# laser-tag.net
KiCad netlist of a schematic drawn in EAGLE
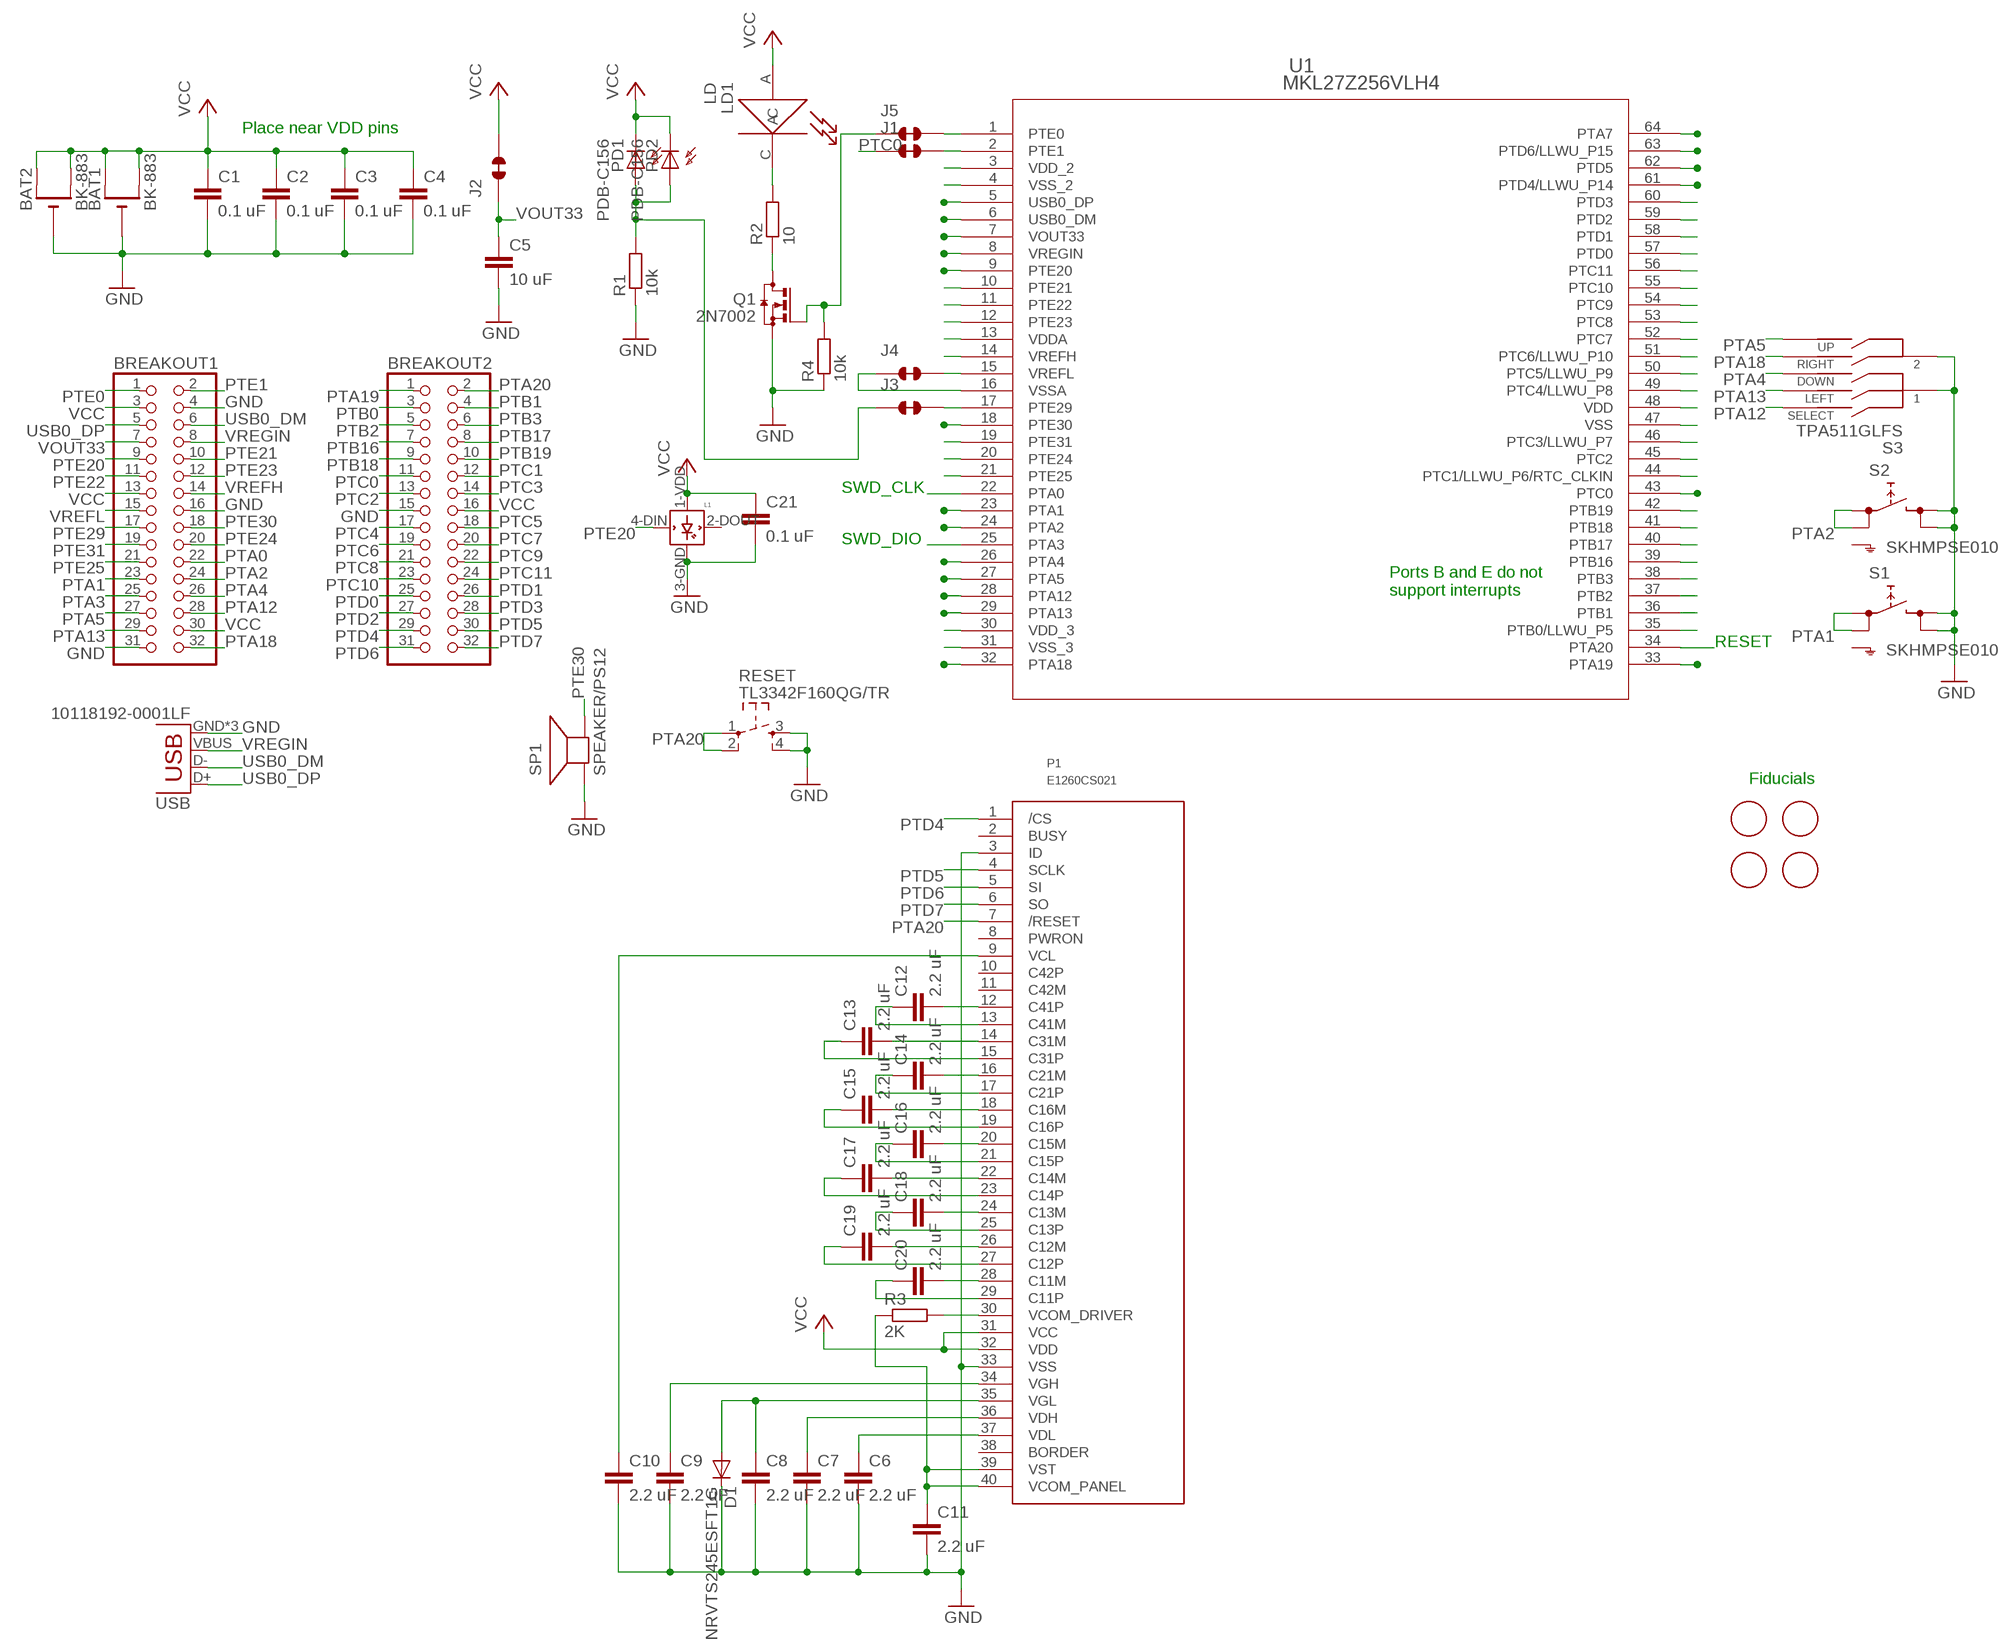
[diagram p0: schematic, sheet 1]

(export (version "E")
  (design (tool "Eeschema 10.0.6"))
  (components
    (comp (ref "BAT1")
      (value "BK-883")
      (footprint "eagle-import:CR2032-SMD")
      (libsource (lib "eagle-import") (part "CR2032SMT"))
    )
    (comp (ref "BAT2")
      (value "BK-883")
      (footprint "eagle-import:CR2032-SMD")
      (libsource (lib "eagle-import") (part "CR2032SMT"))
    )
    (comp (ref "BREAKOUT1")
      (value "PINHD-2X16")
      (footprint "eagle-import:2X16")
      (libsource (lib "eagle-import") (part "PINHD-2X16"))
    )
    (comp (ref "BREAKOUT2")
      (value "PINHD-2X16")
      (footprint "eagle-import:2X16")
      (libsource (lib "eagle-import") (part "PINHD-2X16"))
    )
    (comp (ref "C1")
      (value "0.1 uF")
      (footprint "eagle-import:C0603K")
      (libsource (lib "eagle-import") (part "C-EUC0603K"))
    )
    (comp (ref "C2")
      (value "0.1 uF")
      (footprint "eagle-import:C0603K")
      (libsource (lib "eagle-import") (part "C-EUC0603K"))
    )
    (comp (ref "C3")
      (value "0.1 uF")
      (footprint "eagle-import:C0603K")
      (libsource (lib "eagle-import") (part "C-EUC0603K"))
    )
    (comp (ref "C4")
      (value "0.1 uF")
      (footprint "eagle-import:C0603K")
      (libsource (lib "eagle-import") (part "C-EUC0603K"))
    )
    (comp (ref "C5")
      (value "10 uF")
      (footprint "eagle-import:C0603K")
      (libsource (lib "eagle-import") (part "C-EUC0603K"))
    )
    (comp (ref "C6")
      (value "2.2 uF")
      (footprint "eagle-import:C0603K")
      (libsource (lib "eagle-import") (part "C-EUC0603K"))
    )
    (comp (ref "C7")
      (value "2.2 uF")
      (footprint "eagle-import:C0603K")
      (libsource (lib "eagle-import") (part "C-EUC0603K"))
    )
    (comp (ref "C8")
      (value "2.2 uF")
      (footprint "eagle-import:C0603K")
      (libsource (lib "eagle-import") (part "C-EUC0603K"))
    )
    (comp (ref "C9")
      (value "2.2 uF")
      (footprint "eagle-import:C0603K")
      (libsource (lib "eagle-import") (part "C-EUC0603K"))
    )
    (comp (ref "C10")
      (value "2.2 uF")
      (footprint "eagle-import:C0603K")
      (libsource (lib "eagle-import") (part "C-EUC0603K"))
    )
    (comp (ref "C11")
      (value "2.2 uF")
      (footprint "eagle-import:C0603K")
      (libsource (lib "eagle-import") (part "C-EUC0603K"))
    )
    (comp (ref "C12")
      (value "2.2 uF")
      (footprint "eagle-import:C0603K")
      (libsource (lib "eagle-import") (part "C-EUC0603K"))
    )
    (comp (ref "C13")
      (value "2.2 uF")
      (footprint "eagle-import:C0603K")
      (libsource (lib "eagle-import") (part "C-EUC0603K"))
    )
    (comp (ref "C14")
      (value "2.2 uF")
      (footprint "eagle-import:C0603K")
      (libsource (lib "eagle-import") (part "C-EUC0603K"))
    )
    (comp (ref "C15")
      (value "2.2 uF")
      (footprint "eagle-import:C0603K")
      (libsource (lib "eagle-import") (part "C-EUC0603K"))
    )
    (comp (ref "C16")
      (value "2.2 uF")
      (footprint "eagle-import:C0603K")
      (libsource (lib "eagle-import") (part "C-EUC0603K"))
    )
    (comp (ref "C17")
      (value "2.2 uF")
      (footprint "eagle-import:C0603K")
      (libsource (lib "eagle-import") (part "C-EUC0603K"))
    )
    (comp (ref "C18")
      (value "2.2 uF")
      (footprint "eagle-import:C0603K")
      (libsource (lib "eagle-import") (part "C-EUC0603K"))
    )
    (comp (ref "C19")
      (value "2.2 uF")
      (footprint "eagle-import:C0603K")
      (libsource (lib "eagle-import") (part "C-EUC0603K"))
    )
    (comp (ref "C20")
      (value "2.2 uF")
      (footprint "eagle-import:C0603K")
      (libsource (lib "eagle-import") (part "C-EUC0603K"))
    )
    (comp (ref "C21")
      (value "0.1 uF")
      (footprint "eagle-import:C0603K")
      (libsource (lib "eagle-import") (part "C-EUC0603K"))
    )
    (comp (ref "D1")
      (value "NRVTS245ESFT1G")
      (footprint "eagle-import:SOD-123_MINI-SMA")
      (libsource (lib "eagle-import") (part "CGRM400-G1"))
    )
    (comp (ref "J1")
      (value "JUMPER_SOLDER_1X2_CLOSED")
      (footprint "eagle-import:JUMPER_SOLDER_1X2_CLOSED")
      (libsource (lib "eagle-import") (part "JUMPER_SOLDER_1X2_CLOSED"))
    )
    (comp (ref "J2")
      (value "JUMPER_SOLDER_1X2_CLOSED")
      (footprint "eagle-import:JUMPER_SOLDER_1X2_CLOSED")
      (libsource (lib "eagle-import") (part "JUMPER_SOLDER_1X2_CLOSED"))
    )
    (comp (ref "J3")
      (value "JUMPER_SOLDER_1X2_CLOSED")
      (footprint "eagle-import:JUMPER_SOLDER_1X2_CLOSED")
      (libsource (lib "eagle-import") (part "JUMPER_SOLDER_1X2_CLOSED"))
    )
    (comp (ref "J4")
      (value "JUMPER_SOLDER_1X2_CLOSED")
      (footprint "eagle-import:JUMPER_SOLDER_1X2_CLOSED")
      (libsource (lib "eagle-import") (part "JUMPER_SOLDER_1X2_CLOSED"))
    )
    (comp (ref "J5")
      (value "JUMPER_SOLDER_1X2_CLOSED")
      (footprint "eagle-import:JUMPER_SOLDER_1X2_CLOSED")
      (libsource (lib "eagle-import") (part "JUMPER_SOLDER_1X2_CLOSED"))
    )
    (comp (ref "L1")
      (value "WS2812B")
      (footprint "eagle-import:WS2812B")
      (libsource (lib "eagle-import") (part "WS2812B"))
    )
    (comp (ref "LD1")
      (value "LD")
      (footprint "eagle-import:LD-FLUSH-WITH-JUMPER")
      (libsource (lib "eagle-import") (part "LD"))
    )
    (comp (ref "P1")
      (value "E1260CS021")
      (footprint "eagle-import:E1260CS021_SLOT")
      (libsource (lib "eagle-import") (part "E1260CS021"))
    )
    (comp (ref "PD1")
      (value "PDB-C156")
      (footprint "eagle-import:PDB-C156-FLUSH")
      (libsource (lib "eagle-import") (part "PDB-C156"))
    )
    (comp (ref "PD2")
      (value "PDB-C156")
      (footprint "eagle-import:PDB-C156-FLUSH")
      (libsource (lib "eagle-import") (part "PDB-C156"))
    )
    (comp (ref "Q1")
      (value "2N7002")
      (footprint "eagle-import:SOT23")
      (libsource (lib "eagle-import") (part "BSS123"))
    )
    (comp (ref "R1")
      (value "10k")
      (footprint "eagle-import:R0603")
      (libsource (lib "eagle-import") (part "R-EU_R0603"))
    )
    (comp (ref "R2")
      (value "10")
      (footprint "eagle-import:R0603")
      (libsource (lib "eagle-import") (part "R-EU_R0603"))
    )
    (comp (ref "R3")
      (value "2K")
      (footprint "eagle-import:R0603")
      (libsource (lib "eagle-import") (part "R-EU_R0603"))
    )
    (comp (ref "R4")
      (value "10k")
      (footprint "eagle-import:R0603")
      (libsource (lib "eagle-import") (part "R-EU_R0603"))
    )
    (comp (ref "RESET")
      (value "TL3342F160QG/TR")
      (footprint "eagle-import:SW_TACT_SMALL")
      (libsource (lib "eagle-import") (part "SW_TACT_4P"))
    )
    (comp (ref "S1")
      (value "SKHMPSE010")
      (footprint "eagle-import:SKHMPXE010")
      (libsource (lib "eagle-import") (part "SKHMPE010S"))
    )
    (comp (ref "S2")
      (value "SKHMPSE010")
      (footprint "eagle-import:SKHMPXE010")
      (libsource (lib "eagle-import") (part "SKHMPE010S"))
    )
    (comp (ref "S3")
      (value "TPA511GLFS")
      (footprint "eagle-import:TPA511GLFS")
      (libsource (lib "eagle-import") (part "TPA511GLFS"))
    )
    (comp (ref "SP1")
      (value "SPEAKER/PS12")
      (footprint "eagle-import:PS12")
      (libsource (lib "eagle-import") (part "SPEAKER/PS12"))
    )
    (comp (ref "U$1")
      (value "FIDUCIAL")
      (footprint "eagle-import:FIDUCIAL_1MM")
      (libsource (lib "eagle-import") (part "FIDUCIAL"))
    )
    (comp (ref "U$2")
      (value "FIDUCIAL")
      (footprint "eagle-import:FIDUCIAL_1MM")
      (libsource (lib "eagle-import") (part "FIDUCIAL"))
    )
    (comp (ref "U$3")
      (value "FIDUCIAL")
      (footprint "eagle-import:FIDUCIAL_1MM")
      (libsource (lib "eagle-import") (part "FIDUCIAL"))
    )
    (comp (ref "U$4")
      (value "FIDUCIAL")
      (footprint "eagle-import:FIDUCIAL_1MM")
      (libsource (lib "eagle-import") (part "FIDUCIAL"))
    )
    (comp (ref "U1")
      (value "MKL27Z256VLH4")
      (footprint "eagle-import:LQFP-64_10X10X1.6")
      (fields (field (name "MANUFACTURER_PART_NUMBER") "mkl27z256vlh4"))
      (libsource (lib "eagle-import") (part "MKL27Z256VLH4"))
    )
    (comp (ref "USB")
      (value "10118192-0001LF")
      (footprint "eagle-import:USB-MICROB")
      (libsource (lib "eagle-import") (part "USB-MICROB"))
    )
  )
  (nets
    (net (code "1") (name "/PTA0") (class "Default")
      (node (ref "BREAKOUT1") (pin "22") (pinfunction "22_22") (pintype "passive"))
      (node (ref "U1") (pin "22") (pinfunction "PTA0_22") (pintype "bidirectional"))
    )
    (net (code "2") (name "/PTA1") (class "Default")
      (node (ref "BREAKOUT1") (pin "23") (pinfunction "23_23") (pintype "passive"))
      (node (ref "S1") (pin "1") (pinfunction "1.1_1") (pintype "passive"))
      (node (ref "S1") (pin "2") (pinfunction "1.2_2") (pintype "passive"))
      (node (ref "U1") (pin "23") (pinfunction "PTA1_23") (pintype "bidirectional"))
    )
    (net (code "3") (name "/PTA2") (class "Default")
      (node (ref "BREAKOUT1") (pin "24") (pinfunction "24_24") (pintype "passive"))
      (node (ref "S2") (pin "1") (pinfunction "1.1_1") (pintype "passive"))
      (node (ref "S2") (pin "2") (pinfunction "1.2_2") (pintype "passive"))
      (node (ref "U1") (pin "24") (pinfunction "PTA2_24") (pintype "bidirectional"))
    )
    (net (code "4") (name "/PTA3") (class "Default")
      (node (ref "BREAKOUT1") (pin "25") (pinfunction "25_25") (pintype "passive"))
      (node (ref "U1") (pin "25") (pinfunction "PTA3_25") (pintype "bidirectional"))
    )
    (net (code "5") (name "/PTA4") (class "Default")
      (node (ref "BREAKOUT1") (pin "26") (pinfunction "26_26") (pintype "passive"))
      (node (ref "S3") (pin "4") (pinfunction "DOWN_4") (pintype "bidirectional"))
      (node (ref "U1") (pin "26") (pinfunction "PTA4_26") (pintype "bidirectional"))
    )
    (net (code "6") (name "/PTA5") (class "Default")
      (node (ref "BREAKOUT1") (pin "27") (pinfunction "27_27") (pintype "passive"))
      (node (ref "S3") (pin "3") (pinfunction "UP_3") (pintype "bidirectional"))
      (node (ref "U1") (pin "27") (pinfunction "PTA5_27") (pintype "bidirectional"))
    )
    (net (code "7") (name "/PTA12") (class "Default")
      (node (ref "BREAKOUT1") (pin "28") (pinfunction "28_28") (pintype "passive"))
      (node (ref "S3") (pin "5") (pinfunction "SELECT_5") (pintype "bidirectional"))
      (node (ref "U1") (pin "28") (pinfunction "PTA12_28") (pintype "bidirectional"))
    )
    (net (code "8") (name "/PTA13") (class "Default")
      (node (ref "BREAKOUT1") (pin "29") (pinfunction "29_29") (pintype "passive"))
      (node (ref "S3") (pin "7") (pinfunction "LEFT_7") (pintype "bidirectional"))
      (node (ref "U1") (pin "29") (pinfunction "PTA13_29") (pintype "bidirectional"))
    )
    (net (code "9") (name "/PTA18") (class "Default")
      (node (ref "BREAKOUT1") (pin "32") (pinfunction "32_32") (pintype "passive"))
      (node (ref "S3") (pin "6") (pinfunction "RIGHT_6") (pintype "bidirectional"))
      (node (ref "U1") (pin "32") (pinfunction "PTA18_32") (pintype "bidirectional"))
    )
    (net (code "10") (name "/PTA19") (class "Default")
      (node (ref "BREAKOUT2") (pin "1") (pinfunction "1_1") (pintype "passive"))
      (node (ref "U1") (pin "33") (pinfunction "PTA19_33") (pintype "bidirectional"))
    )
    (net (code "11") (name "/PTA20") (class "Default")
      (node (ref "BREAKOUT2") (pin "2") (pinfunction "2_2") (pintype "passive"))
      (node (ref "P1") (pin "7") (pinfunction "/RESET_7") (pintype "input"))
      (node (ref "RESET") (pin "1") (pinfunction "1_1") (pintype "passive"))
      (node (ref "RESET") (pin "2") (pinfunction "2_2") (pintype "passive"))
      (node (ref "U1") (pin "34") (pinfunction "PTA20_34") (pintype "bidirectional"))
    )
    (net (code "12") (name "/PTB0") (class "Default")
      (node (ref "BREAKOUT2") (pin "3") (pinfunction "3_3") (pintype "passive"))
      (node (ref "U1") (pin "35") (pinfunction "PTB0/LLWU_P5_35") (pintype "bidirectional"))
    )
    (net (code "13") (name "/PTB1") (class "Default")
      (node (ref "BREAKOUT2") (pin "4") (pinfunction "4_4") (pintype "passive"))
      (node (ref "U1") (pin "36") (pinfunction "PTB1_36") (pintype "bidirectional"))
    )
    (net (code "14") (name "/PTB2") (class "Default")
      (node (ref "BREAKOUT2") (pin "5") (pinfunction "5_5") (pintype "passive"))
      (node (ref "U1") (pin "37") (pinfunction "PTB2_37") (pintype "bidirectional"))
    )
    (net (code "15") (name "/PTB3") (class "Default")
      (node (ref "BREAKOUT2") (pin "6") (pinfunction "6_6") (pintype "passive"))
      (node (ref "U1") (pin "38") (pinfunction "PTB3_38") (pintype "bidirectional"))
    )
    (net (code "16") (name "/PTB16") (class "Default")
      (node (ref "BREAKOUT2") (pin "7") (pinfunction "7_7") (pintype "passive"))
      (node (ref "U1") (pin "39") (pinfunction "PTB16_39") (pintype "bidirectional"))
    )
    (net (code "17") (name "/PTB17") (class "Default")
      (node (ref "BREAKOUT2") (pin "8") (pinfunction "8_8") (pintype "passive"))
      (node (ref "U1") (pin "40") (pinfunction "PTB17_40") (pintype "bidirectional"))
    )
    (net (code "18") (name "/PTB18") (class "Default")
      (node (ref "BREAKOUT2") (pin "9") (pinfunction "9_9") (pintype "passive"))
      (node (ref "U1") (pin "41") (pinfunction "PTB18_41") (pintype "bidirectional"))
    )
    (net (code "19") (name "/PTB19") (class "Default")
      (node (ref "BREAKOUT2") (pin "10") (pinfunction "10_10") (pintype "passive"))
      (node (ref "U1") (pin "42") (pinfunction "PTB19_42") (pintype "bidirectional"))
    )
    (net (code "20") (name "/PTC0") (class "Default")
      (node (ref "BREAKOUT2") (pin "11") (pinfunction "11_11") (pintype "passive"))
      (node (ref "J1") (pin "1") (pinfunction "1_1") (pintype "passive"))
      (node (ref "U1") (pin "43") (pinfunction "PTC0_43") (pintype "bidirectional"))
    )
    (net (code "21") (name "/PTC1") (class "Default")
      (node (ref "BREAKOUT2") (pin "12") (pinfunction "12_12") (pintype "passive"))
      (node (ref "U1") (pin "44") (pinfunction "PTC1/LLWU_P6/RTC_CLKIN_44") (pintype "bidirectional"))
    )
    (net (code "22") (name "/PTC2") (class "Default")
      (node (ref "BREAKOUT2") (pin "13") (pinfunction "13_13") (pintype "passive"))
      (node (ref "U1") (pin "45") (pinfunction "PTC2_45") (pintype "bidirectional"))
    )
    (net (code "23") (name "/PTC3") (class "Default")
      (node (ref "BREAKOUT2") (pin "14") (pinfunction "14_14") (pintype "passive"))
      (node (ref "U1") (pin "46") (pinfunction "PTC3/LLWU_P7_46") (pintype "bidirectional"))
    )
    (net (code "24") (name "/PTC4") (class "Default")
      (node (ref "BREAKOUT2") (pin "17") (pinfunction "17_17") (pintype "passive"))
      (node (ref "U1") (pin "49") (pinfunction "PTC4/LLWU_P8_49") (pintype "bidirectional"))
    )
    (net (code "25") (name "/PTC5") (class "Default")
      (node (ref "BREAKOUT2") (pin "18") (pinfunction "18_18") (pintype "passive"))
      (node (ref "U1") (pin "50") (pinfunction "PTC5/LLWU_P9_50") (pintype "bidirectional"))
    )
    (net (code "26") (name "/PTC6") (class "Default")
      (node (ref "BREAKOUT2") (pin "19") (pinfunction "19_19") (pintype "passive"))
      (node (ref "U1") (pin "51") (pinfunction "PTC6/LLWU_P10_51") (pintype "bidirectional"))
    )
    (net (code "27") (name "/PTC7") (class "Default")
      (node (ref "BREAKOUT2") (pin "20") (pinfunction "20_20") (pintype "passive"))
      (node (ref "U1") (pin "52") (pinfunction "PTC7_52") (pintype "bidirectional"))
    )
    (net (code "28") (name "/PTC8") (class "Default")
      (node (ref "BREAKOUT2") (pin "21") (pinfunction "21_21") (pintype "passive"))
      (node (ref "U1") (pin "53") (pinfunction "PTC8_53") (pintype "bidirectional"))
    )
    (net (code "29") (name "/PTC9") (class "Default")
      (node (ref "BREAKOUT2") (pin "22") (pinfunction "22_22") (pintype "passive"))
      (node (ref "U1") (pin "54") (pinfunction "PTC9_54") (pintype "bidirectional"))
    )
    (net (code "30") (name "/PTC10") (class "Default")
      (node (ref "BREAKOUT2") (pin "23") (pinfunction "23_23") (pintype "passive"))
      (node (ref "U1") (pin "55") (pinfunction "PTC10_55") (pintype "bidirectional"))
    )
    (net (code "31") (name "/PTC11") (class "Default")
      (node (ref "BREAKOUT2") (pin "24") (pinfunction "24_24") (pintype "passive"))
      (node (ref "U1") (pin "56") (pinfunction "PTC11_56") (pintype "bidirectional"))
    )
    (net (code "32") (name "/PTD0") (class "Default")
      (node (ref "BREAKOUT2") (pin "25") (pinfunction "25_25") (pintype "passive"))
      (node (ref "U1") (pin "57") (pinfunction "PTD0_57") (pintype "bidirectional"))
    )
    (net (code "33") (name "/PTD1") (class "Default")
      (node (ref "BREAKOUT2") (pin "26") (pinfunction "26_26") (pintype "passive"))
      (node (ref "U1") (pin "58") (pinfunction "PTD1_58") (pintype "bidirectional"))
    )
    (net (code "34") (name "/PTD2") (class "Default")
      (node (ref "BREAKOUT2") (pin "27") (pinfunction "27_27") (pintype "passive"))
      (node (ref "U1") (pin "59") (pinfunction "PTD2_59") (pintype "bidirectional"))
    )
    (net (code "35") (name "/PTD3") (class "Default")
      (node (ref "BREAKOUT2") (pin "28") (pinfunction "28_28") (pintype "passive"))
      (node (ref "U1") (pin "60") (pinfunction "PTD3_60") (pintype "bidirectional"))
    )
    (net (code "36") (name "/PTD4") (class "Default")
      (node (ref "BREAKOUT2") (pin "29") (pinfunction "29_29") (pintype "passive"))
      (node (ref "P1") (pin "1") (pinfunction "/CS_1") (pintype "input"))
      (node (ref "U1") (pin "61") (pinfunction "PTD4/LLWU_P14_61") (pintype "bidirectional"))
    )
    (net (code "37") (name "/PTD5") (class "Default")
      (node (ref "BREAKOUT2") (pin "30") (pinfunction "30_30") (pintype "passive"))
      (node (ref "P1") (pin "4") (pinfunction "SCLK_4") (pintype "input"))
      (node (ref "U1") (pin "62") (pinfunction "PTD5_62") (pintype "bidirectional"))
    )
    (net (code "38") (name "/PTD6") (class "Default")
      (node (ref "BREAKOUT2") (pin "31") (pinfunction "31_31") (pintype "passive"))
      (node (ref "P1") (pin "5") (pinfunction "SI_5") (pintype "input"))
      (node (ref "U1") (pin "63") (pinfunction "PTD6/LLWU_P15_63") (pintype "bidirectional"))
    )
    (net (code "39") (name "/PTD7") (class "Default")
      (node (ref "BREAKOUT2") (pin "32") (pinfunction "32_32") (pintype "passive"))
      (node (ref "P1") (pin "6") (pinfunction "SO_6") (pintype "output"))
      (node (ref "U1") (pin "64") (pinfunction "PTA7_64") (pintype "bidirectional"))
    )
    (net (code "40") (name "/PTE0") (class "Default")
      (node (ref "BREAKOUT1") (pin "1") (pinfunction "1_1") (pintype "passive"))
      (node (ref "J5") (pin "2") (pinfunction "2_2") (pintype "passive"))
      (node (ref "U1") (pin "1") (pinfunction "PTE0_1") (pintype "bidirectional"))
    )
    (net (code "41") (name "/PTE1") (class "Default")
      (node (ref "BREAKOUT1") (pin "2") (pinfunction "2_2") (pintype "passive"))
      (node (ref "J1") (pin "2") (pinfunction "2_2") (pintype "passive"))
      (node (ref "U1") (pin "2") (pinfunction "PTE1_2") (pintype "bidirectional"))
    )
    (net (code "42") (name "/PTE20") (class "Default")
      (node (ref "BREAKOUT1") (pin "9") (pinfunction "9_9") (pintype "passive"))
      (node (ref "L1") (pin "4-DIN") (pinfunction "DIN_4-DIN") (pintype "input"))
      (node (ref "U1") (pin "9") (pinfunction "PTE20_9") (pintype "bidirectional"))
    )
    (net (code "43") (name "/PTE21") (class "Default")
      (node (ref "BREAKOUT1") (pin "10") (pinfunction "10_10") (pintype "passive"))
      (node (ref "U1") (pin "10") (pinfunction "PTE21_10") (pintype "bidirectional"))
    )
    (net (code "44") (name "/PTE22") (class "Default")
      (node (ref "BREAKOUT1") (pin "11") (pinfunction "11_11") (pintype "passive"))
      (node (ref "U1") (pin "11") (pinfunction "PTE22_11") (pintype "bidirectional"))
    )
    (net (code "45") (name "/PTE23") (class "Default")
      (node (ref "BREAKOUT1") (pin "12") (pinfunction "12_12") (pintype "passive"))
      (node (ref "U1") (pin "12") (pinfunction "PTE23_12") (pintype "bidirectional"))
    )
    (net (code "46") (name "/PTE24") (class "Default")
      (node (ref "BREAKOUT1") (pin "20") (pinfunction "20_20") (pintype "passive"))
      (node (ref "U1") (pin "20") (pinfunction "PTE24_20") (pintype "bidirectional"))
    )
    (net (code "47") (name "/PTE25") (class "Default")
      (node (ref "BREAKOUT1") (pin "21") (pinfunction "21_21") (pintype "passive"))
      (node (ref "U1") (pin "21") (pinfunction "PTE25_21") (pintype "bidirectional"))
    )
    (net (code "48") (name "/PTE29") (class "Default")
      (node (ref "BREAKOUT1") (pin "17") (pinfunction "17_17") (pintype "passive"))
      (node (ref "J3") (pin "2") (pinfunction "2_2") (pintype "passive"))
      (node (ref "U1") (pin "17") (pinfunction "PTE29_17") (pintype "bidirectional"))
    )
    (net (code "49") (name "/PTE30") (class "Default")
      (node (ref "BREAKOUT1") (pin "18") (pinfunction "18_18") (pintype "passive"))
      (node (ref "SP1") (pin "P$2") (pinfunction "-_P$2") (pintype "passive"))
      (node (ref "U1") (pin "18") (pinfunction "PTE30_18") (pintype "bidirectional"))
    )
    (net (code "50") (name "/PTE31") (class "Default")
      (node (ref "BREAKOUT1") (pin "19") (pinfunction "19_19") (pintype "passive"))
      (node (ref "U1") (pin "19") (pinfunction "PTE31_19") (pintype "bidirectional"))
    )
    (net (code "51") (name "/USB0_DM") (class "Default")
      (node (ref "BREAKOUT1") (pin "6") (pinfunction "6_6") (pintype "passive"))
      (node (ref "U1") (pin "6") (pinfunction "USB0_DM_6") (pintype "passive"))
      (node (ref "USB") (pin "D-") (pinfunction "D-_D-") (pintype "bidirectional"))
    )
    (net (code "52") (name "/USB0_DP") (class "Default")
      (node (ref "BREAKOUT1") (pin "5") (pinfunction "5_5") (pintype "passive"))
      (node (ref "U1") (pin "5") (pinfunction "USB0_DP_5") (pintype "passive"))
      (node (ref "USB") (pin "D+") (pinfunction "D+_D+") (pintype "bidirectional"))
    )
    (net (code "53") (name "/VOUT33") (class "Default")
      (node (ref "BREAKOUT1") (pin "7") (pinfunction "7_7") (pintype "passive"))
      (node (ref "C5") (pin "1") (pinfunction "1_1") (pintype "passive"))
      (node (ref "J2") (pin "1") (pinfunction "1_1") (pintype "passive"))
      (node (ref "U1") (pin "7") (pinfunction "VOUT33_7") (pintype "output"))
    )
    (net (code "54") (name "/VREFH") (class "Default")
      (node (ref "BREAKOUT1") (pin "14") (pinfunction "14_14") (pintype "passive"))
      (node (ref "U1") (pin "14") (pinfunction "VREFH_14") (pintype "power_in"))
    )
    (net (code "55") (name "/VREFL") (class "Default")
      (node (ref "BREAKOUT1") (pin "15") (pinfunction "15_15") (pintype "passive"))
      (node (ref "J4") (pin "2") (pinfunction "2_2") (pintype "passive"))
      (node (ref "U1") (pin "15") (pinfunction "VREFL_15") (pintype "power_in"))
    )
    (net (code "56") (name "/VREGIN") (class "Default")
      (node (ref "BREAKOUT1") (pin "8") (pinfunction "8_8") (pintype "passive"))
      (node (ref "U1") (pin "8") (pinfunction "VREGIN_8") (pintype "input"))
      (node (ref "USB") (pin "VBUS") (pinfunction "VBUS_VBUS") (pintype "bidirectional"))
    )
    (net (code "57") (name "GND") (class "Default")
      (node (ref "BAT1") (pin "-") (pinfunction "-_-") (pintype "passive"))
      (node (ref "BAT2") (pin "-") (pinfunction "-_-") (pintype "passive"))
      (node (ref "BREAKOUT1") (pin "16") (pinfunction "16_16") (pintype "passive"))
      (node (ref "BREAKOUT1") (pin "31") (pinfunction "31_31") (pintype "passive"))
      (node (ref "BREAKOUT1") (pin "4") (pinfunction "4_4") (pintype "passive"))
      (node (ref "BREAKOUT2") (pin "15") (pinfunction "15_15") (pintype "passive"))
      (node (ref "C1") (pin "2") (pinfunction "2_2") (pintype "passive"))
      (node (ref "C10") (pin "2") (pinfunction "2_2") (pintype "passive"))
      (node (ref "C11") (pin "2") (pinfunction "2_2") (pintype "passive"))
      (node (ref "C2") (pin "2") (pinfunction "2_2") (pintype "passive"))
      (node (ref "C21") (pin "2") (pinfunction "2_2") (pintype "passive"))
      (node (ref "C3") (pin "2") (pinfunction "2_2") (pintype "passive"))
      (node (ref "C4") (pin "2") (pinfunction "2_2") (pintype "passive"))
      (node (ref "C5") (pin "2") (pinfunction "2_2") (pintype "passive"))
      (node (ref "C6") (pin "2") (pinfunction "2_2") (pintype "passive"))
      (node (ref "C7") (pin "2") (pinfunction "2_2") (pintype "passive"))
      (node (ref "C8") (pin "2") (pinfunction "2_2") (pintype "passive"))
      (node (ref "C9") (pin "2") (pinfunction "2_2") (pintype "passive"))
      (node (ref "D1") (pin "C") (pinfunction "C_C") (pintype "passive"))
      (node (ref "J4") (pin "1") (pinfunction "1_1") (pintype "passive"))
      (node (ref "L1") (pin "3-GND") (pinfunction "GND_3-GND") (pintype "bidirectional"))
      (node (ref "P1") (pin "3") (pinfunction "ID_3") (pintype "input"))
      (node (ref "P1") (pin "33") (pinfunction "VSS_33") (pintype "power_in"))
      (node (ref "Q1") (pin "2") (pinfunction "S_2") (pintype "passive"))
      (node (ref "R1") (pin "1") (pinfunction "1_1") (pintype "passive"))
      (node (ref "R4") (pin "1") (pinfunction "1_1") (pintype "passive"))
      (node (ref "RESET") (pin "3") (pinfunction "3_3") (pintype "passive"))
      (node (ref "RESET") (pin "4") (pinfunction "4_4") (pintype "passive"))
      (node (ref "S1") (pin "3") (pinfunction "2.1_3") (pintype "passive"))
      (node (ref "S1") (pin "4") (pinfunction "2.2_4") (pintype "passive"))
      (node (ref "S2") (pin "3") (pinfunction "2.1_3") (pintype "passive"))
      (node (ref "S2") (pin "4") (pinfunction "2.2_4") (pintype "passive"))
      (node (ref "S3") (pin "1") (pinfunction "1_1") (pintype "bidirectional"))
      (node (ref "S3") (pin "2") (pinfunction "2_2") (pintype "bidirectional"))
      (node (ref "SP1") (pin "P$1") (pinfunction "+_P$1") (pintype "passive"))
      (node (ref "U1") (pin "16") (pinfunction "VSSA_16") (pintype "power_in"))
      (node (ref "U1") (pin "31") (pinfunction "VSS_3_31") (pintype "power_in"))
      (node (ref "U1") (pin "4") (pinfunction "VSS_2_4") (pintype "power_in"))
      (node (ref "U1") (pin "47") (pinfunction "VSS_47") (pintype "power_in"))
      (node (ref "USB") (pin "GND") (pinfunction "GND_GND") (pintype "bidirectional"))
      (node (ref "USB") (pin "MT1") (pinfunction "GND_MT1") (pintype "bidirectional"))
      (node (ref "USB") (pin "MT2") (pinfunction "GND_MT2") (pintype "bidirectional"))
    )
    (net (code "58") (name "Net-(J3-Pad1)") (class "Default")
      (node (ref "J3") (pin "1") (pinfunction "1_1") (pintype "passive"))
      (node (ref "PD1") (pin "A") (pinfunction "A_A") (pintype "passive"))
      (node (ref "PD2") (pin "A") (pinfunction "A_A") (pintype "passive"))
      (node (ref "R1") (pin "2") (pinfunction "2_2") (pintype "passive"))
    )
    (net (code "59") (name "Net-(LD1-PadC)") (class "Default")
      (node (ref "LD1") (pin "C") (pinfunction "C_C") (pintype "passive"))
      (node (ref "R2") (pin "2") (pinfunction "2_2") (pintype "passive"))
    )
    (net (code "60") (name "Net-(P1-C11M)") (class "Default")
      (node (ref "C20") (pin "2") (pinfunction "2_2") (pintype "passive"))
      (node (ref "P1") (pin "28") (pinfunction "C11M_28") (pintype "passive"))
    )
    (net (code "61") (name "Net-(P1-C11P)") (class "Default")
      (node (ref "C20") (pin "1") (pinfunction "1_1") (pintype "passive"))
      (node (ref "P1") (pin "29") (pinfunction "C11P_29") (pintype "passive"))
    )
    (net (code "62") (name "Net-(P1-C12M)") (class "Default")
      (node (ref "C19") (pin "2") (pinfunction "2_2") (pintype "passive"))
      (node (ref "P1") (pin "26") (pinfunction "C12M_26") (pintype "passive"))
    )
    (net (code "63") (name "Net-(P1-C12P)") (class "Default")
      (node (ref "C19") (pin "1") (pinfunction "1_1") (pintype "passive"))
      (node (ref "P1") (pin "27") (pinfunction "C12P_27") (pintype "passive"))
    )
    (net (code "64") (name "Net-(P1-C13M)") (class "Default")
      (node (ref "C18") (pin "2") (pinfunction "2_2") (pintype "passive"))
      (node (ref "P1") (pin "24") (pinfunction "C13M_24") (pintype "passive"))
    )
    (net (code "65") (name "Net-(P1-C13P)") (class "Default")
      (node (ref "C18") (pin "1") (pinfunction "1_1") (pintype "passive"))
      (node (ref "P1") (pin "25") (pinfunction "C13P_25") (pintype "passive"))
    )
    (net (code "66") (name "Net-(P1-C14M)") (class "Default")
      (node (ref "C17") (pin "2") (pinfunction "2_2") (pintype "passive"))
      (node (ref "P1") (pin "22") (pinfunction "C14M_22") (pintype "passive"))
    )
    (net (code "67") (name "Net-(P1-C14P)") (class "Default")
      (node (ref "C17") (pin "1") (pinfunction "1_1") (pintype "passive"))
      (node (ref "P1") (pin "23") (pinfunction "C14P_23") (pintype "passive"))
    )
    (net (code "68") (name "Net-(P1-C15M)") (class "Default")
      (node (ref "C16") (pin "2") (pinfunction "2_2") (pintype "passive"))
      (node (ref "P1") (pin "20") (pinfunction "C15M_20") (pintype "passive"))
    )
    (net (code "69") (name "Net-(P1-C15P)") (class "Default")
      (node (ref "C16") (pin "1") (pinfunction "1_1") (pintype "passive"))
      (node (ref "P1") (pin "21") (pinfunction "C15P_21") (pintype "passive"))
    )
    (net (code "70") (name "Net-(P1-C16M)") (class "Default")
      (node (ref "C15") (pin "2") (pinfunction "2_2") (pintype "passive"))
      (node (ref "P1") (pin "18") (pinfunction "C16M_18") (pintype "passive"))
    )
    (net (code "71") (name "Net-(P1-C16P)") (class "Default")
      (node (ref "C15") (pin "1") (pinfunction "1_1") (pintype "passive"))
      (node (ref "P1") (pin "19") (pinfunction "C16P_19") (pintype "passive"))
    )
    (net (code "72") (name "Net-(P1-C21M)") (class "Default")
      (node (ref "C14") (pin "2") (pinfunction "2_2") (pintype "passive"))
      (node (ref "P1") (pin "16") (pinfunction "C21M_16") (pintype "passive"))
    )
    (net (code "73") (name "Net-(P1-C21P)") (class "Default")
      (node (ref "C14") (pin "1") (pinfunction "1_1") (pintype "passive"))
      (node (ref "P1") (pin "17") (pinfunction "C21P_17") (pintype "passive"))
    )
    (net (code "74") (name "Net-(P1-C31M)") (class "Default")
      (node (ref "C13") (pin "2") (pinfunction "2_2") (pintype "passive"))
      (node (ref "P1") (pin "14") (pinfunction "C31M_14") (pintype "passive"))
    )
    (net (code "75") (name "Net-(P1-C31P)") (class "Default")
      (node (ref "C13") (pin "1") (pinfunction "1_1") (pintype "passive"))
      (node (ref "P1") (pin "15") (pinfunction "C31P_15") (pintype "passive"))
    )
    (net (code "76") (name "Net-(P1-C41M)") (class "Default")
      (node (ref "C12") (pin "1") (pinfunction "1_1") (pintype "passive"))
      (node (ref "P1") (pin "13") (pinfunction "C41M_13") (pintype "passive"))
    )
    (net (code "77") (name "Net-(P1-C41P)") (class "Default")
      (node (ref "C12") (pin "2") (pinfunction "2_2") (pintype "passive"))
      (node (ref "P1") (pin "12") (pinfunction "C41P_12") (pintype "passive"))
    )
    (net (code "78") (name "Net-(P1-VCL)") (class "Default")
      (node (ref "C10") (pin "1") (pinfunction "1_1") (pintype "passive"))
      (node (ref "P1") (pin "9") (pinfunction "VCL_9") (pintype "passive"))
    )
    (net (code "79") (name "Net-(P1-VCOM_DRIVER)") (class "Default")
      (node (ref "P1") (pin "30") (pinfunction "VCOM_DRIVER_30") (pintype "passive"))
      (node (ref "R3") (pin "2") (pinfunction "2_2") (pintype "passive"))
    )
    (net (code "80") (name "Net-(P1-VCOM_PANEL)") (class "Default")
      (node (ref "C11") (pin "1") (pinfunction "1_1") (pintype "passive"))
      (node (ref "P1") (pin "39") (pinfunction "VST_39") (pintype "power_in"))
      (node (ref "P1") (pin "40") (pinfunction "VCOM_PANEL_40") (pintype "passive"))
      (node (ref "R3") (pin "1") (pinfunction "1_1") (pintype "passive"))
    )
    (net (code "81") (name "Net-(P1-VDH)") (class "Default")
      (node (ref "C7") (pin "1") (pinfunction "1_1") (pintype "passive"))
      (node (ref "P1") (pin "36") (pinfunction "VDH_36") (pintype "passive"))
    )
    (net (code "82") (name "Net-(P1-VDL)") (class "Default")
      (node (ref "C6") (pin "1") (pinfunction "1_1") (pintype "passive"))
      (node (ref "P1") (pin "37") (pinfunction "VDL_37") (pintype "passive"))
    )
    (net (code "83") (name "Net-(P1-VGH)") (class "Default")
      (node (ref "C9") (pin "1") (pinfunction "1_1") (pintype "passive"))
      (node (ref "P1") (pin "34") (pinfunction "VGH_34") (pintype "passive"))
    )
    (net (code "84") (name "Net-(P1-VGL)") (class "Default")
      (node (ref "C8") (pin "1") (pinfunction "1_1") (pintype "passive"))
      (node (ref "D1") (pin "A") (pinfunction "A_A") (pintype "passive"))
      (node (ref "P1") (pin "35") (pinfunction "VGL_35") (pintype "passive"))
    )
    (net (code "85") (name "Net-(Q1-D)") (class "Default")
      (node (ref "Q1") (pin "3") (pinfunction "D_3") (pintype "passive"))
      (node (ref "R2") (pin "1") (pinfunction "1_1") (pintype "passive"))
    )
    (net (code "86") (name "Net-(Q1-G)") (class "Default")
      (node (ref "J5") (pin "1") (pinfunction "1_1") (pintype "passive"))
      (node (ref "Q1") (pin "1") (pinfunction "G_1") (pintype "passive"))
      (node (ref "R4") (pin "2") (pinfunction "2_2") (pintype "passive"))
    )
    (net (code "87") (name "VCC") (class "Default")
      (node (ref "BAT1") (pin "+$1") (pinfunction "+_+$1") (pintype "passive"))
      (node (ref "BAT1") (pin "+$2") (pinfunction "+1_+$2") (pintype "passive"))
      (node (ref "BAT2") (pin "+$1") (pinfunction "+_+$1") (pintype "passive"))
      (node (ref "BAT2") (pin "+$2") (pinfunction "+1_+$2") (pintype "passive"))
      (node (ref "BREAKOUT1") (pin "13") (pinfunction "13_13") (pintype "passive"))
      (node (ref "BREAKOUT1") (pin "3") (pinfunction "3_3") (pintype "passive"))
      (node (ref "BREAKOUT1") (pin "30") (pinfunction "30_30") (pintype "passive"))
      (node (ref "BREAKOUT2") (pin "16") (pinfunction "16_16") (pintype "passive"))
      (node (ref "C1") (pin "1") (pinfunction "1_1") (pintype "passive"))
      (node (ref "C2") (pin "1") (pinfunction "1_1") (pintype "passive"))
      (node (ref "C21") (pin "1") (pinfunction "1_1") (pintype "passive"))
      (node (ref "C3") (pin "1") (pinfunction "1_1") (pintype "passive"))
      (node (ref "C4") (pin "1") (pinfunction "1_1") (pintype "passive"))
      (node (ref "J2") (pin "2") (pinfunction "2_2") (pintype "passive"))
      (node (ref "L1") (pin "1-VDD") (pinfunction "VDD_1-VDD") (pintype "bidirectional"))
      (node (ref "LD1") (pin "A") (pinfunction "A_A") (pintype "passive"))
      (node (ref "P1") (pin "31") (pinfunction "VCC_31") (pintype "power_in"))
      (node (ref "P1") (pin "32") (pinfunction "VDD_32") (pintype "power_in"))
      (node (ref "PD1") (pin "C") (pinfunction "C_C") (pintype "passive"))
      (node (ref "PD2") (pin "C") (pinfunction "C_C") (pintype "passive"))
      (node (ref "U1") (pin "13") (pinfunction "VDDA_13") (pintype "power_in"))
      (node (ref "U1") (pin "3") (pinfunction "VDD_2_3") (pintype "power_in"))
      (node (ref "U1") (pin "30") (pinfunction "VDD_3_30") (pintype "power_in"))
      (node (ref "U1") (pin "48") (pinfunction "VDD_48") (pintype "power_in"))
    )
    (net (code "88") (name "unconnected-(L1-DOUT-Pad2-DOUT)") (class "Default")
      (node (ref "L1") (pin "2-DOUT") (pinfunction "DOUT_2-DOUT") (pintype "output"))
    )
    (net (code "89") (name "unconnected-(P1-BORDER-Pad38)") (class "Default")
      (node (ref "P1") (pin "38") (pinfunction "BORDER_38") (pintype "input"))
    )
    (net (code "90") (name "unconnected-(P1-BUSY-Pad2)") (class "Default")
      (node (ref "P1") (pin "2") (pinfunction "BUSY_2") (pintype "output"))
    )
    (net (code "91") (name "unconnected-(P1-C42M-Pad11)") (class "Default")
      (node (ref "P1") (pin "11") (pinfunction "C42M_11") (pintype "no_connect"))
    )
    (net (code "92") (name "unconnected-(P1-C42P-Pad10)") (class "Default")
      (node (ref "P1") (pin "10") (pinfunction "C42P_10") (pintype "no_connect"))
    )
    (net (code "93") (name "unconnected-(P1-PWRON-Pad8)") (class "Default")
      (node (ref "P1") (pin "8") (pinfunction "PWRON_8") (pintype "no_connect"))
    )
    (net (code "94") (name "unconnected-(S1-SH-Pad5)") (class "Default")
      (node (ref "S1") (pin "5") (pinfunction "SH_5") (pintype "passive"))
    )
    (net (code "95") (name "unconnected-(S2-SH-Pad5)") (class "Default")
      (node (ref "S2") (pin "5") (pinfunction "SH_5") (pintype "passive"))
    )
  )
)
